# Slave_DA.net
KiCad netlist of a schematic drawn in Altium Designer
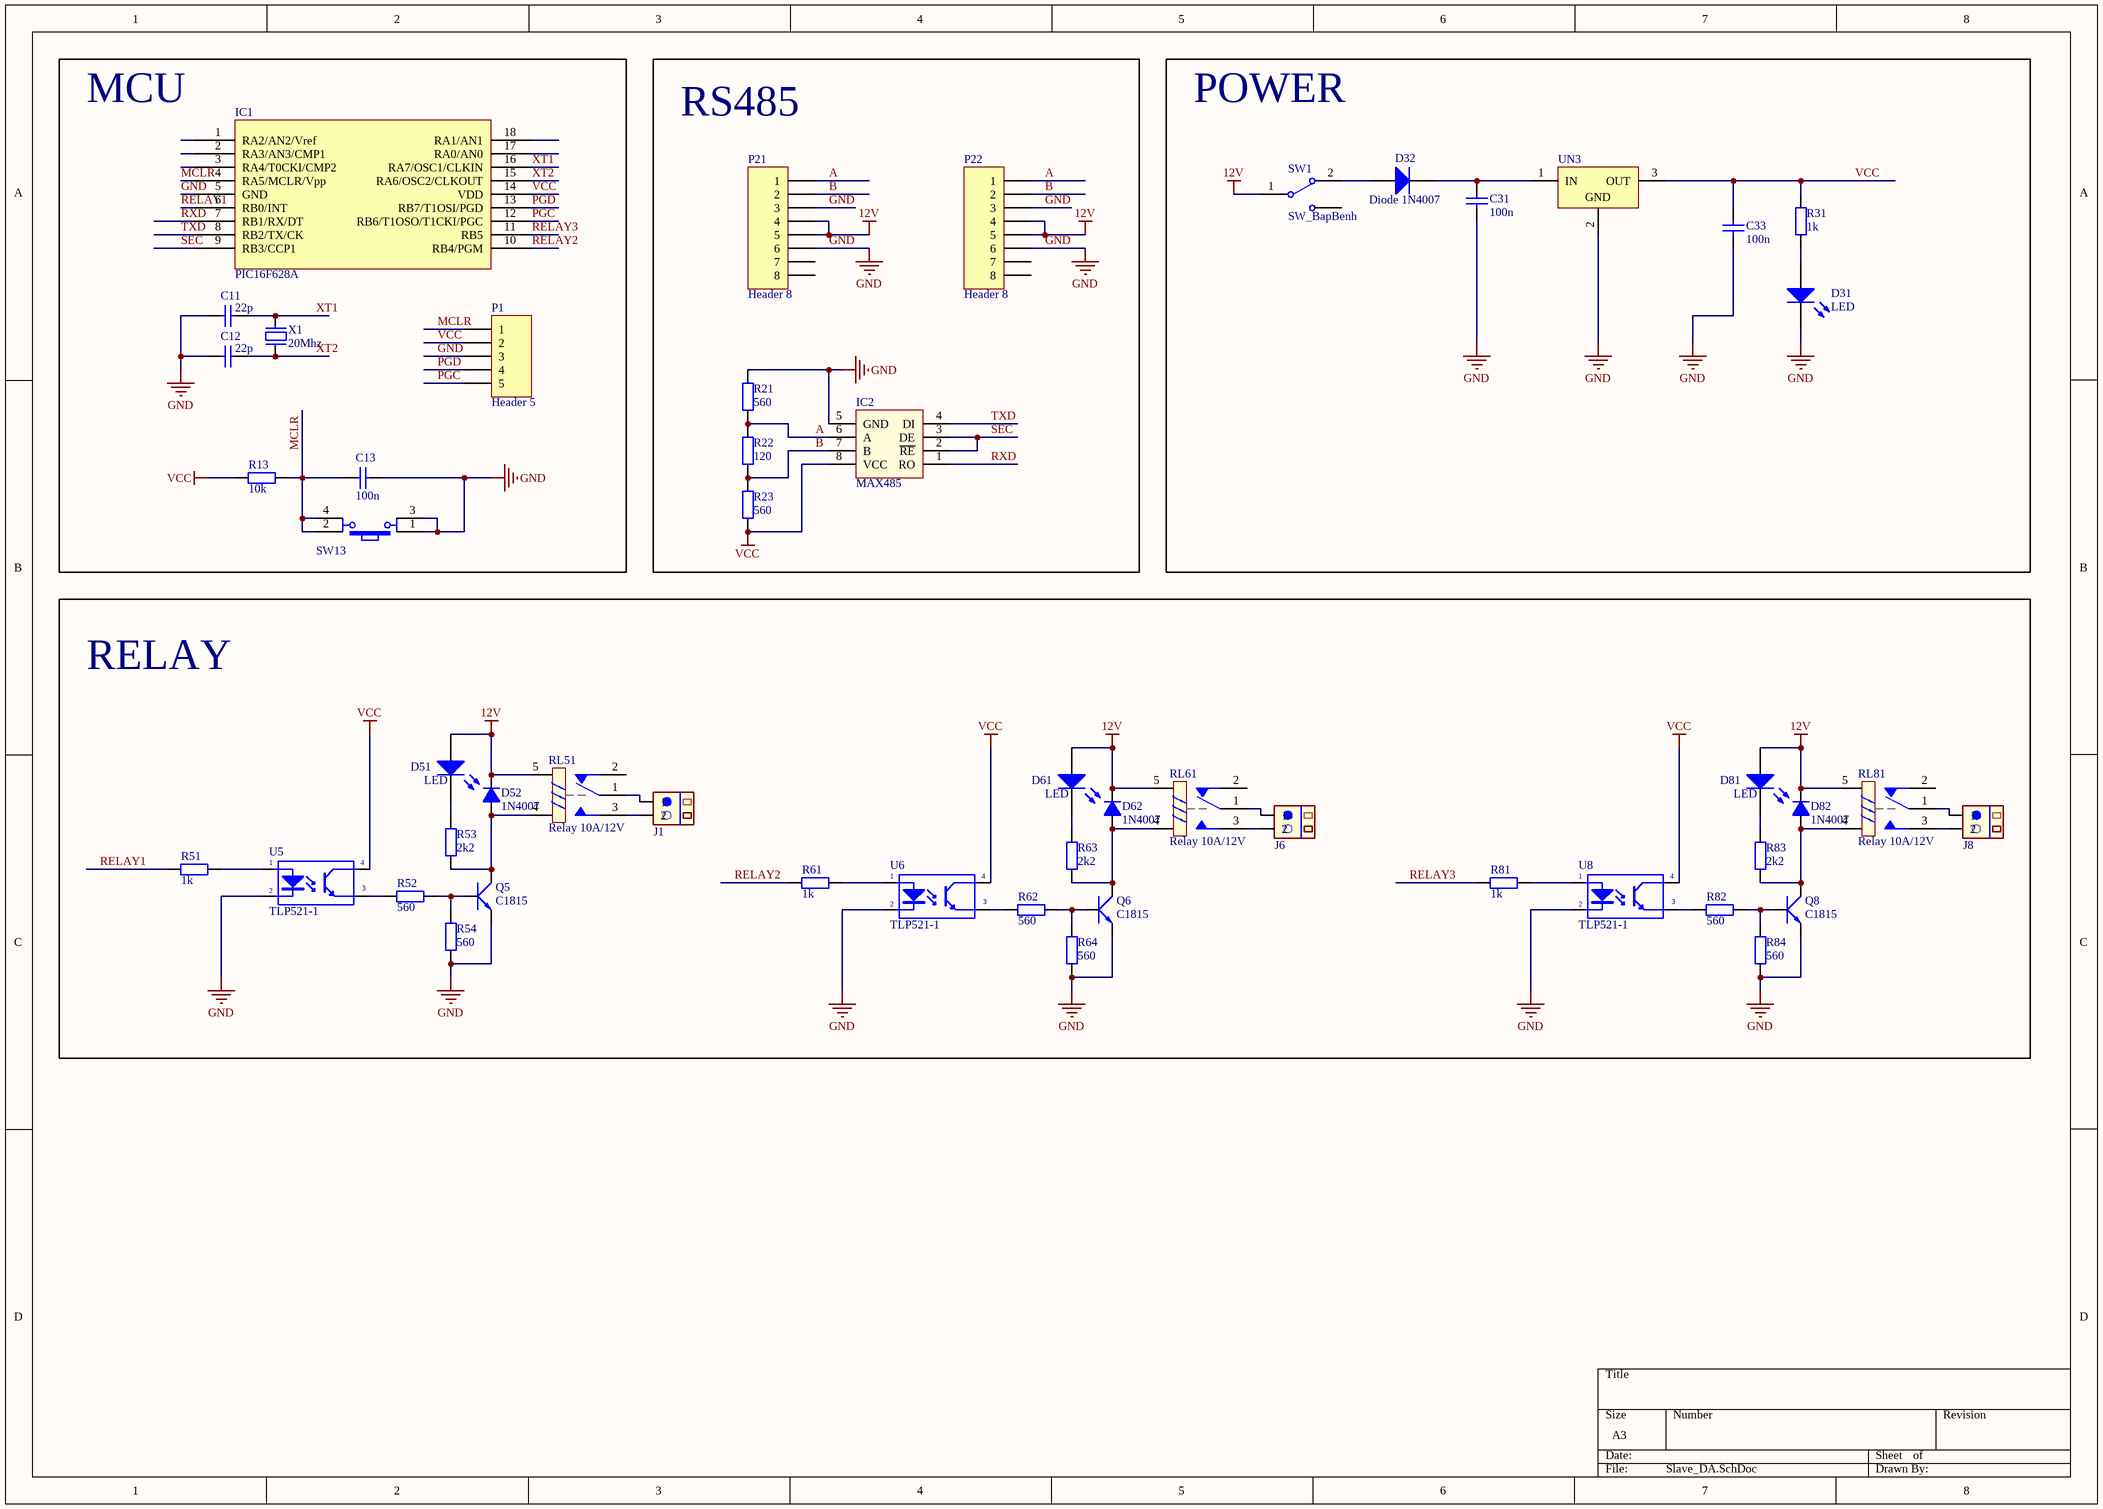
[diagram p0: Slave_DA.SchDoc]

(export (version "E")
  (design (tool "Eeschema 10.0.6"))
  (components
    (comp (ref "C11")
      (value "22p")
      (footprint "C-NP-0805")
      (description "Non-polarized Capacitor")
      (fields (field (name "Comment") "Cap Non-pol") (field (name "PUBLISHER") "Altium Limited"))
      (libsource (lib "THG") (part "Cap Non-pol"))
    )
    (comp (ref "C12")
      (value "22p")
      (footprint "C-NP-0805")
      (description "Non-polarized Capacitor")
      (fields (field (name "Comment") "Cap Non-pol") (field (name "PUBLISHER") "Altium Limited"))
      (libsource (lib "THG") (part "Cap Non-pol"))
    )
    (comp (ref "C13")
      (value "100n")
      (footprint "CAP_SMD_0805")
      (description "Capacitor")
      (fields (field (name "Comment") "Capacitor Ceramic") (field (name "PUBLISHER") "Altium Limited"))
      (libsource (lib "THG") (part "CapSMD"))
    )
    (comp (ref "C31")
      (value "100n")
      (footprint "C-NP-0805")
      (description "Non-polarized Capacitor")
      (fields (field (name "Comment") "Cap Non-pol") (field (name "PUBLISHER") "Altium Limited"))
      (libsource (lib "THG") (part "Cap Non-pol"))
    )
    (comp (ref "C33")
      (value "100n")
      (footprint "C-NP-0805")
      (description "Non-polarized Capacitor")
      (fields (field (name "Comment") "Cap Non-pol") (field (name "PUBLISHER") "Altium Limited"))
      (libsource (lib "THG") (part "Cap Non-pol"))
    )
    (comp (ref "D31")
      (value "LED")
      (footprint "LED-0805 RED")
      (description "Typical LED")
      (fields (field (name "PUBLISHER") "Altium Limited"))
      (libsource (lib "THG") (part "LED"))
    )
    (comp (ref "D32")
      (value "Diode 1N4007")
      (footprint "DO-41")
      (description "1 Amp General Purpose Rectifier")
      (fields (field (name "PUBLISHER") "Altium Limited"))
      (libsource (lib "hphonglib") (part "Diode 1N4007"))
    )
    (comp (ref "D51")
      (value "LED")
      (footprint "LED-0 5mm RED")
      (description "Typical LED")
      (fields (field (name "PUBLISHER") "Altium Limited"))
      (libsource (lib "THG") (part "LED"))
    )
    (comp (ref "D52")
      (value "1N4007")
      (footprint "D1A")
      (description "Diode 1A")
      (libsource (lib "syhaunguyen") (part "D1A"))
    )
    (comp (ref "D61")
      (value "LED")
      (footprint "LED-0 5mm RED")
      (description "Typical LED")
      (fields (field (name "PUBLISHER") "Altium Limited"))
      (libsource (lib "THG") (part "LED"))
    )
    (comp (ref "D62")
      (value "1N4007")
      (footprint "D1A")
      (description "Diode 1A")
      (libsource (lib "syhaunguyen") (part "D1A"))
    )
    (comp (ref "D81")
      (value "LED")
      (footprint "LED-0 5mm RED")
      (description "Typical LED")
      (fields (field (name "PUBLISHER") "Altium Limited"))
      (libsource (lib "THG") (part "LED"))
    )
    (comp (ref "D82")
      (value "1N4007")
      (footprint "D1A")
      (description "Diode 1A")
      (libsource (lib "syhaunguyen") (part "D1A"))
    )
    (comp (ref "IC1")
      (value "PIC16F628A")
      (footprint "DIP18/W0.3")
      (libsource (lib "THG") (part "PIC16F628A"))
    )
    (comp (ref "IC2")
      (value "MAX485")
      (footprint "DIP8/W0.3")
      (description "RS232 - RS485 (Same sn75176)")
      (libsource (lib "syhaunguyen") (part "MAX485"))
    )
    (comp (ref "J1")
      (value "CON.Domino2")
      (footprint "DOMINO 2B")
      (description "2 pins Domino Header")
      (fields (field (name "PUBLISHER") "Hoang Nguyen"))
      (libsource (lib "THG") (part "CON.Domino2"))
    )
    (comp (ref "J6")
      (value "CON.Domino2")
      (footprint "DOMINO 2B")
      (description "2 pins Domino Header")
      (fields (field (name "PUBLISHER") "Hoang Nguyen"))
      (libsource (lib "THG") (part "CON.Domino2"))
    )
    (comp (ref "J8")
      (value "CON.Domino2")
      (footprint "DOMINO 2B")
      (description "2 pins Domino Header")
      (fields (field (name "PUBLISHER") "Hoang Nguyen"))
      (libsource (lib "THG") (part "CON.Domino2"))
    )
    (comp (ref "P1")
      (value "Header 5")
      (footprint "Header 5")
      (description "Header, 5-Pin")
      (fields (field (name "PUBLISHER") "Altium Limited"))
      (libsource (lib "THG") (part "Header 5"))
    )
    (comp (ref "P21")
      (value "Header 8")
      (footprint "RJ11")
      (description "Header, 8-Pin")
      (fields (field (name "PUBLISHER") "Altium Limited"))
      (libsource (lib "THG") (part "Header 8"))
    )
    (comp (ref "P22")
      (value "Header 8")
      (footprint "RJ11")
      (description "Header, 8-Pin")
      (fields (field (name "PUBLISHER") "Altium Limited"))
      (libsource (lib "THG") (part "Header 8"))
    )
    (comp (ref "Q5")
      (value "C1815")
      (footprint "QTO-92")
      (description "NPN 600mW, ECB")
      (libsource (lib "syhaunguyen") (part "C1815"))
    )
    (comp (ref "Q6")
      (value "C1815")
      (footprint "QTO-92")
      (description "NPN 600mW, ECB")
      (libsource (lib "syhaunguyen") (part "C1815"))
    )
    (comp (ref "Q8")
      (value "C1815")
      (footprint "QTO-92")
      (description "NPN 600mW, ECB")
      (libsource (lib "syhaunguyen") (part "C1815"))
    )
    (comp (ref "R13")
      (value "10k")
      (footprint "DIEN TRO 0805")
      (description "RES_0805")
      (fields (field (name "Comment") "RES_SMD_0805") (field (name "PUBLISHER") "Altium Limited"))
      (libsource (lib "THG") (part "RES_SMD_0805"))
    )
    (comp (ref "R21")
      (value "560")
      (footprint "DIEN TRO 0805")
      (description "RES_0805")
      (fields (field (name "Comment") "RES_SMD_0805") (field (name "PUBLISHER") "Altium Limited"))
      (libsource (lib "") (part "RES_SMD_0805_2"))
    )
    (comp (ref "R22")
      (value "120")
      (footprint "DIEN TRO 0805")
      (description "RES_0805")
      (fields (field (name "Comment") "RES_SMD_0805") (field (name "PUBLISHER") "Altium Limited"))
      (libsource (lib "") (part "RES_SMD_0805_2"))
    )
    (comp (ref "R23")
      (value "560")
      (footprint "DIEN TRO 0805")
      (description "RES_0805")
      (fields (field (name "Comment") "RES_SMD_0805") (field (name "PUBLISHER") "Altium Limited"))
      (libsource (lib "") (part "RES_SMD_0805_2"))
    )
    (comp (ref "R31")
      (value "1k")
      (footprint "DIEN TRO 0805")
      (description "RES_0805")
      (fields (field (name "Comment") "RES_SMD_0805") (field (name "PUBLISHER") "Altium Limited"))
      (libsource (lib "") (part "RES_SMD_0805_2"))
    )
    (comp (ref "R51")
      (value "1k")
      (footprint "DIEN TRO 0805")
      (description "RES_0805")
      (fields (field (name "Comment") "RES_SMD_0805") (field (name "PUBLISHER") "Altium Limited"))
      (libsource (lib "THG") (part "RES_SMD_0805"))
    )
    (comp (ref "R52")
      (value "560")
      (footprint "DIEN TRO 0805")
      (description "RES_0805")
      (fields (field (name "Comment") "RES_SMD_0805") (field (name "PUBLISHER") "Altium Limited"))
      (libsource (lib "THG") (part "RES_SMD_0805"))
    )
    (comp (ref "R53")
      (value "2k2")
      (footprint "DIEN TRO 0805")
      (description "RES_0805")
      (fields (field (name "Comment") "RES_SMD_0805") (field (name "PUBLISHER") "Altium Limited"))
      (libsource (lib "") (part "RES_SMD_0805_1"))
    )
    (comp (ref "R54")
      (value "560")
      (footprint "DIEN TRO 0805")
      (description "RES_0805")
      (fields (field (name "Comment") "RES_SMD_0805") (field (name "PUBLISHER") "Altium Limited"))
      (libsource (lib "") (part "RES_SMD_0805_1"))
    )
    (comp (ref "R61")
      (value "1k")
      (footprint "DIEN TRO 0805")
      (description "RES_0805")
      (fields (field (name "Comment") "RES_SMD_0805") (field (name "PUBLISHER") "Altium Limited"))
      (libsource (lib "THG") (part "RES_SMD_0805"))
    )
    (comp (ref "R62")
      (value "560")
      (footprint "DIEN TRO 0805")
      (description "RES_0805")
      (fields (field (name "Comment") "RES_SMD_0805") (field (name "PUBLISHER") "Altium Limited"))
      (libsource (lib "THG") (part "RES_SMD_0805"))
    )
    (comp (ref "R63")
      (value "2k2")
      (footprint "DIEN TRO 0805")
      (description "RES_0805")
      (fields (field (name "Comment") "RES_SMD_0805") (field (name "PUBLISHER") "Altium Limited"))
      (libsource (lib "") (part "RES_SMD_0805_1"))
    )
    (comp (ref "R64")
      (value "560")
      (footprint "DIEN TRO 0805")
      (description "RES_0805")
      (fields (field (name "Comment") "RES_SMD_0805") (field (name "PUBLISHER") "Altium Limited"))
      (libsource (lib "") (part "RES_SMD_0805_1"))
    )
    (comp (ref "R81")
      (value "1k")
      (footprint "DIEN TRO 0805")
      (description "RES_0805")
      (fields (field (name "Comment") "RES_SMD_0805") (field (name "PUBLISHER") "Altium Limited"))
      (libsource (lib "THG") (part "RES_SMD_0805"))
    )
    (comp (ref "R82")
      (value "560")
      (footprint "DIEN TRO 0805")
      (description "RES_0805")
      (fields (field (name "Comment") "RES_SMD_0805") (field (name "PUBLISHER") "Altium Limited"))
      (libsource (lib "THG") (part "RES_SMD_0805"))
    )
    (comp (ref "R83")
      (value "2k2")
      (footprint "DIEN TRO 0805")
      (description "RES_0805")
      (fields (field (name "Comment") "RES_SMD_0805") (field (name "PUBLISHER") "Altium Limited"))
      (libsource (lib "") (part "RES_SMD_0805_1"))
    )
    (comp (ref "R84")
      (value "560")
      (footprint "DIEN TRO 0805")
      (description "RES_0805")
      (fields (field (name "Comment") "RES_SMD_0805") (field (name "PUBLISHER") "Altium Limited"))
      (libsource (lib "") (part "RES_SMD_0805_1"))
    )
    (comp (ref "RL51")
      (value "Relay 10A/12V")
      (footprint "RL_SPDT_10A")
      (description "Relay SPDT,10A - 12VDC 5 Pin")
      (libsource (lib "syhaunguyen") (part "Relay 1"))
    )
    (comp (ref "RL61")
      (value "Relay 10A/12V")
      (footprint "RL_SPDT_10A")
      (description "Relay SPDT,10A - 12VDC 5 Pin")
      (libsource (lib "syhaunguyen") (part "Relay 1"))
    )
    (comp (ref "RL81")
      (value "Relay 10A/12V")
      (footprint "RL_SPDT_10A")
      (description "Relay SPDT,10A - 12VDC 5 Pin")
      (libsource (lib "syhaunguyen") (part "Relay 1"))
    )
    (comp (ref "SW1")
      (value "SW_BapBenh")
      (footprint "SW_Bapbenh")
      (libsource (lib "THG") (part "SW_BapBenh"))
    )
    (comp (ref "SW13")
      (value "SW7")
      (footprint "SW4")
      (description "Switch button 4 pin")
      (libsource (lib "syhaunguyen") (part "SW4"))
    )
    (comp (ref "U5")
      (value "TLP521-1")
      (footprint "DIP4/W0.3")
      (description "Single Opto")
      (libsource (lib "syhaunguyen") (part "TLP521-1"))
    )
    (comp (ref "U6")
      (value "TLP521-1")
      (footprint "DIP4/W0.3")
      (description "Single Opto")
      (libsource (lib "syhaunguyen") (part "TLP521-1"))
    )
    (comp (ref "U8")
      (value "TLP521-1")
      (footprint "DIP4/W0.3")
      (description "Single Opto")
      (libsource (lib "syhaunguyen") (part "TLP521-1"))
    )
    (comp (ref "UN3")
      (value "L78M05CP")
      (footprint "QTO-220")
      (description "Positive Voltage Regulator")
      (fields (field (name "PUBLISHER") "Altium Limited"))
      (libsource (lib "syhaunguyen") (part "L78M05CP"))
    )
    (comp (ref "X1")
      (value "20Mhz")
      (footprint "XT2")
      (description "Crystal For all Crystal 2pin.")
      (libsource (lib "syhaunguyen") (part "XT2"))
    )
  )
  (nets
    (net (code "1") (name "/A") (class "Default")
      (node (ref "IC2") (pin "6") (pinfunction "A_6") (pintype "passive"))
      (node (ref "P21") (pin "1") (pinfunction "1_1") (pintype "passive"))
      (node (ref "P22") (pin "1") (pinfunction "1_1") (pintype "passive"))
      (node (ref "R21") (pin "1") (pinfunction "1_1") (pintype "passive"))
      (node (ref "R22") (pin "2") (pinfunction "2_2") (pintype "passive"))
    )
    (net (code "2") (name "/B") (class "Default")
      (node (ref "IC2") (pin "7") (pinfunction "B_7") (pintype "passive"))
      (node (ref "P21") (pin "2") (pinfunction "2_2") (pintype "passive"))
      (node (ref "P22") (pin "2") (pinfunction "2_2") (pintype "passive"))
      (node (ref "R22") (pin "1") (pinfunction "1_1") (pintype "passive"))
      (node (ref "R23") (pin "2") (pinfunction "2_2") (pintype "passive"))
    )
    (net (code "3") (name "/MCLR") (class "Default")
      (node (ref "C13") (pin "2") (pinfunction "2_2") (pintype "passive"))
      (node (ref "IC1") (pin "4") (pinfunction "RA5/MCLR/Vpp_4") (pintype "passive"))
      (node (ref "P1") (pin "1") (pinfunction "1_1") (pintype "passive"))
      (node (ref "R13") (pin "1") (pinfunction "1_1") (pintype "passive"))
      (node (ref "SW13") (pin "2") (pintype "passive"))
      (node (ref "SW13") (pin "4") (pintype "passive"))
    )
    (net (code "4") (name "/PGC") (class "Default")
      (node (ref "IC1") (pin "12") (pinfunction "RB6/T1OSO/T1CKI/PGC_12") (pintype "passive"))
      (node (ref "P1") (pin "5") (pinfunction "5_5") (pintype "passive"))
    )
    (net (code "5") (name "/PGD") (class "Default")
      (node (ref "IC1") (pin "13") (pinfunction "RB7/T1OSI/PGD_13") (pintype "passive"))
      (node (ref "P1") (pin "4") (pinfunction "4_4") (pintype "passive"))
    )
    (net (code "6") (name "/RELAY1") (class "Default")
      (node (ref "IC1") (pin "6") (pinfunction "RB0/INT_6") (pintype "passive"))
      (node (ref "R51") (pin "2") (pinfunction "2_2") (pintype "passive"))
    )
    (net (code "7") (name "/RELAY2") (class "Default")
      (node (ref "IC1") (pin "10") (pinfunction "RB4/PGM_10") (pintype "passive"))
      (node (ref "R61") (pin "2") (pinfunction "2_2") (pintype "passive"))
    )
    (net (code "8") (name "/RELAY3") (class "Default")
      (node (ref "IC1") (pin "11") (pinfunction "RB5_11") (pintype "passive"))
      (node (ref "R81") (pin "2") (pinfunction "2_2") (pintype "passive"))
    )
    (net (code "9") (name "/RXD") (class "Default")
      (node (ref "IC1") (pin "7") (pinfunction "RB1/RX/DT_7") (pintype "passive"))
      (node (ref "IC2") (pin "1") (pinfunction "RO_1") (pintype "passive"))
    )
    (net (code "10") (name "/SEC") (class "Default")
      (node (ref "IC1") (pin "9") (pinfunction "RB3/CCP1_9") (pintype "passive"))
      (node (ref "IC2") (pin "2") (pinfunction "~{RE}_2") (pintype "passive"))
      (node (ref "IC2") (pin "3") (pinfunction "DE_3") (pintype "passive"))
    )
    (net (code "11") (name "/TXD") (class "Default")
      (node (ref "IC1") (pin "8") (pinfunction "RB2/TX/CK_8") (pintype "passive"))
      (node (ref "IC2") (pin "4") (pinfunction "DI_4") (pintype "passive"))
    )
    (net (code "12") (name "/XT1") (class "Default")
      (node (ref "C11") (pin "1") (pinfunction "1_1") (pintype "passive"))
      (node (ref "IC1") (pin "16") (pinfunction "RA7/OSC1/CLKIN_16") (pintype "passive"))
      (node (ref "X1") (pin "2") (pinfunction "2_2") (pintype "passive"))
    )
    (net (code "13") (name "/XT2") (class "Default")
      (node (ref "C12") (pin "1") (pinfunction "1_1") (pintype "passive"))
      (node (ref "IC1") (pin "15") (pinfunction "RA6/OSC2/CLKOUT_15") (pintype "passive"))
      (node (ref "X1") (pin "1") (pinfunction "1_1") (pintype "passive"))
    )
    (net (code "14") (name "12V") (class "Default")
      (node (ref "D51") (pin "1") (pinfunction "A_1") (pintype "passive"))
      (node (ref "D52") (pin "2") (pinfunction "K_2") (pintype "passive"))
      (node (ref "D61") (pin "1") (pinfunction "A_1") (pintype "passive"))
      (node (ref "D62") (pin "2") (pinfunction "K_2") (pintype "passive"))
      (node (ref "D81") (pin "1") (pinfunction "A_1") (pintype "passive"))
      (node (ref "D82") (pin "2") (pinfunction "K_2") (pintype "passive"))
      (node (ref "P21") (pin "4") (pinfunction "4_4") (pintype "passive"))
      (node (ref "P21") (pin "5") (pinfunction "5_5") (pintype "passive"))
      (node (ref "P22") (pin "4") (pinfunction "4_4") (pintype "passive"))
      (node (ref "P22") (pin "5") (pinfunction "5_5") (pintype "passive"))
      (node (ref "RL51") (pin "5") (pinfunction "5_5") (pintype "passive"))
      (node (ref "RL61") (pin "5") (pinfunction "5_5") (pintype "passive"))
      (node (ref "RL81") (pin "5") (pinfunction "5_5") (pintype "passive"))
      (node (ref "SW1") (pin "1") (pinfunction "1_1") (pintype "passive"))
    )
    (net (code "15") (name "GND") (class "Default")
      (node (ref "C11") (pin "2") (pinfunction "2_2") (pintype "passive"))
      (node (ref "C12") (pin "2") (pinfunction "2_2") (pintype "passive"))
      (node (ref "C13") (pin "1") (pinfunction "1_1") (pintype "passive"))
      (node (ref "C31") (pin "1") (pinfunction "1_1") (pintype "passive"))
      (node (ref "C33") (pin "1") (pinfunction "1_1") (pintype "passive"))
      (node (ref "D31") (pin "2") (pinfunction "K_2") (pintype "passive"))
      (node (ref "IC1") (pin "5") (pinfunction "GND_5") (pintype "passive"))
      (node (ref "IC2") (pin "5") (pinfunction "GND_5") (pintype "passive"))
      (node (ref "P1") (pin "3") (pinfunction "3_3") (pintype "passive"))
      (node (ref "P21") (pin "3") (pinfunction "3_3") (pintype "passive"))
      (node (ref "P21") (pin "6") (pinfunction "6_6") (pintype "passive"))
      (node (ref "P22") (pin "3") (pinfunction "3_3") (pintype "passive"))
      (node (ref "P22") (pin "6") (pinfunction "6_6") (pintype "passive"))
      (node (ref "Q5") (pin "1") (pinfunction "E_1") (pintype "passive"))
      (node (ref "Q6") (pin "1") (pinfunction "E_1") (pintype "passive"))
      (node (ref "Q8") (pin "1") (pinfunction "E_1") (pintype "passive"))
      (node (ref "R21") (pin "2") (pinfunction "2_2") (pintype "passive"))
      (node (ref "R54") (pin "2") (pinfunction "2_2") (pintype "passive"))
      (node (ref "R64") (pin "2") (pinfunction "2_2") (pintype "passive"))
      (node (ref "R84") (pin "2") (pinfunction "2_2") (pintype "passive"))
      (node (ref "SW13") (pin "1") (pintype "passive"))
      (node (ref "SW13") (pin "3") (pintype "passive"))
      (node (ref "U5") (pin "2") (pinfunction "K_2") (pintype "passive"))
      (node (ref "U6") (pin "2") (pinfunction "K_2") (pintype "passive"))
      (node (ref "U8") (pin "2") (pinfunction "K_2") (pintype "passive"))
      (node (ref "UN3") (pin "2") (pinfunction "GND_2") (pintype "power_in"))
    )
    (net (code "16") (name "Net-(D31-A)") (class "Default")
      (node (ref "D31") (pin "1") (pinfunction "A_1") (pintype "passive"))
      (node (ref "R31") (pin "1") (pinfunction "1_1") (pintype "passive"))
    )
    (net (code "17") (name "Net-(D32-A)") (class "Default")
      (node (ref "D32") (pin "1") (pinfunction "A_1") (pintype "passive"))
      (node (ref "SW1") (pin "2") (pinfunction "2_2") (pintype "passive"))
    )
    (net (code "18") (name "Net-(D32-K)") (class "Default")
      (node (ref "C31") (pin "2") (pinfunction "2_2") (pintype "passive"))
      (node (ref "D32") (pin "2") (pinfunction "K_2") (pintype "passive"))
      (node (ref "UN3") (pin "1") (pinfunction "IN_1") (pintype "power_in"))
    )
    (net (code "19") (name "Net-(D51-K)") (class "Default")
      (node (ref "D51") (pin "2") (pinfunction "K_2") (pintype "passive"))
      (node (ref "R53") (pin "1") (pinfunction "1_1") (pintype "passive"))
    )
    (net (code "20") (name "Net-(D52-A)") (class "Default")
      (node (ref "D52") (pin "1") (pinfunction "A_1") (pintype "passive"))
      (node (ref "Q5") (pin "2") (pinfunction "C_2") (pintype "passive"))
      (node (ref "R53") (pin "2") (pinfunction "2_2") (pintype "passive"))
      (node (ref "RL51") (pin "4") (pinfunction "4_4") (pintype "passive"))
    )
    (net (code "21") (name "Net-(D61-K)") (class "Default")
      (node (ref "D61") (pin "2") (pinfunction "K_2") (pintype "passive"))
      (node (ref "R63") (pin "1") (pinfunction "1_1") (pintype "passive"))
    )
    (net (code "22") (name "Net-(D62-A)") (class "Default")
      (node (ref "D62") (pin "1") (pinfunction "A_1") (pintype "passive"))
      (node (ref "Q6") (pin "2") (pinfunction "C_2") (pintype "passive"))
      (node (ref "R63") (pin "2") (pinfunction "2_2") (pintype "passive"))
      (node (ref "RL61") (pin "4") (pinfunction "4_4") (pintype "passive"))
    )
    (net (code "23") (name "Net-(D81-K)") (class "Default")
      (node (ref "D81") (pin "2") (pinfunction "K_2") (pintype "passive"))
      (node (ref "R83") (pin "1") (pinfunction "1_1") (pintype "passive"))
    )
    (net (code "24") (name "Net-(D82-A)") (class "Default")
      (node (ref "D82") (pin "1") (pinfunction "A_1") (pintype "passive"))
      (node (ref "Q8") (pin "2") (pinfunction "C_2") (pintype "passive"))
      (node (ref "R83") (pin "2") (pinfunction "2_2") (pintype "passive"))
      (node (ref "RL81") (pin "4") (pinfunction "4_4") (pintype "passive"))
    )
    (net (code "25") (name "Net-(J1-Pad1)") (class "Default")
      (node (ref "J1") (pin "1") (pinfunction "1_1") (pintype "passive"))
      (node (ref "RL51") (pin "1") (pinfunction "1_1") (pintype "passive"))
    )
    (net (code "26") (name "Net-(J1-Pad2)") (class "Default")
      (node (ref "J1") (pin "2") (pinfunction "2_2") (pintype "passive"))
      (node (ref "RL51") (pin "3") (pinfunction "3_3") (pintype "passive"))
    )
    (net (code "27") (name "Net-(J6-Pad1)") (class "Default")
      (node (ref "J6") (pin "1") (pinfunction "1_1") (pintype "passive"))
      (node (ref "RL61") (pin "1") (pinfunction "1_1") (pintype "passive"))
    )
    (net (code "28") (name "Net-(J6-Pad2)") (class "Default")
      (node (ref "J6") (pin "2") (pinfunction "2_2") (pintype "passive"))
      (node (ref "RL61") (pin "3") (pinfunction "3_3") (pintype "passive"))
    )
    (net (code "29") (name "Net-(J8-Pad1)") (class "Default")
      (node (ref "J8") (pin "1") (pinfunction "1_1") (pintype "passive"))
      (node (ref "RL81") (pin "1") (pinfunction "1_1") (pintype "passive"))
    )
    (net (code "30") (name "Net-(J8-Pad2)") (class "Default")
      (node (ref "J8") (pin "2") (pinfunction "2_2") (pintype "passive"))
      (node (ref "RL81") (pin "3") (pinfunction "3_3") (pintype "passive"))
    )
    (net (code "31") (name "Net-(Q5-B)") (class "Default")
      (node (ref "Q5") (pin "3") (pinfunction "B_3") (pintype "passive"))
      (node (ref "R52") (pin "1") (pinfunction "1_1") (pintype "passive"))
      (node (ref "R54") (pin "1") (pinfunction "1_1") (pintype "passive"))
    )
    (net (code "32") (name "Net-(Q6-B)") (class "Default")
      (node (ref "Q6") (pin "3") (pinfunction "B_3") (pintype "passive"))
      (node (ref "R62") (pin "1") (pinfunction "1_1") (pintype "passive"))
      (node (ref "R64") (pin "1") (pinfunction "1_1") (pintype "passive"))
    )
    (net (code "33") (name "Net-(Q8-B)") (class "Default")
      (node (ref "Q8") (pin "3") (pinfunction "B_3") (pintype "passive"))
      (node (ref "R82") (pin "1") (pinfunction "1_1") (pintype "passive"))
      (node (ref "R84") (pin "1") (pinfunction "1_1") (pintype "passive"))
    )
    (net (code "34") (name "Net-(U5-A)") (class "Default")
      (node (ref "R51") (pin "1") (pinfunction "1_1") (pintype "passive"))
      (node (ref "U5") (pin "1") (pinfunction "A_1") (pintype "passive"))
    )
    (net (code "35") (name "Net-(U5-E)") (class "Default")
      (node (ref "R52") (pin "2") (pinfunction "2_2") (pintype "passive"))
      (node (ref "U5") (pin "3") (pinfunction "E_3") (pintype "passive"))
    )
    (net (code "36") (name "Net-(U6-A)") (class "Default")
      (node (ref "R61") (pin "1") (pinfunction "1_1") (pintype "passive"))
      (node (ref "U6") (pin "1") (pinfunction "A_1") (pintype "passive"))
    )
    (net (code "37") (name "Net-(U6-E)") (class "Default")
      (node (ref "R62") (pin "2") (pinfunction "2_2") (pintype "passive"))
      (node (ref "U6") (pin "3") (pinfunction "E_3") (pintype "passive"))
    )
    (net (code "38") (name "Net-(U8-A)") (class "Default")
      (node (ref "R81") (pin "1") (pinfunction "1_1") (pintype "passive"))
      (node (ref "U8") (pin "1") (pinfunction "A_1") (pintype "passive"))
    )
    (net (code "39") (name "Net-(U8-E)") (class "Default")
      (node (ref "R82") (pin "2") (pinfunction "2_2") (pintype "passive"))
      (node (ref "U8") (pin "3") (pinfunction "E_3") (pintype "passive"))
    )
    (net (code "40") (name "VCC") (class "Default")
      (node (ref "C33") (pin "2") (pinfunction "2_2") (pintype "passive"))
      (node (ref "IC1") (pin "14") (pinfunction "VDD_14") (pintype "passive"))
      (node (ref "IC2") (pin "8") (pinfunction "VCC_8") (pintype "passive"))
      (node (ref "P1") (pin "2") (pinfunction "2_2") (pintype "passive"))
      (node (ref "R13") (pin "2") (pinfunction "2_2") (pintype "passive"))
      (node (ref "R23") (pin "1") (pinfunction "1_1") (pintype "passive"))
      (node (ref "R31") (pin "2") (pinfunction "2_2") (pintype "passive"))
      (node (ref "U5") (pin "4") (pinfunction "C_4") (pintype "passive"))
      (node (ref "U6") (pin "4") (pinfunction "C_4") (pintype "passive"))
      (node (ref "U8") (pin "4") (pinfunction "C_4") (pintype "passive"))
      (node (ref "UN3") (pin "3") (pinfunction "OUT_3") (pintype "power_in"))
    )
    (net (code "41") (name "unconnected-(IC1-RA0{slash}AN0-Pad17)") (class "Default")
      (node (ref "IC1") (pin "17") (pinfunction "RA0/AN0_17") (pintype "passive"))
    )
    (net (code "42") (name "unconnected-(IC1-RA1{slash}AN1-Pad18)") (class "Default")
      (node (ref "IC1") (pin "18") (pinfunction "RA1/AN1_18") (pintype "passive"))
    )
    (net (code "43") (name "unconnected-(IC1-RA2{slash}AN2{slash}Vref-Pad1)") (class "Default")
      (node (ref "IC1") (pin "1") (pinfunction "RA2/AN2/Vref_1") (pintype "passive"))
    )
    (net (code "44") (name "unconnected-(IC1-RA3{slash}AN3{slash}CMP1-Pad2)") (class "Default")
      (node (ref "IC1") (pin "2") (pinfunction "RA3/AN3/CMP1_2") (pintype "passive"))
    )
    (net (code "45") (name "unconnected-(IC1-RA4{slash}T0CKI{slash}CMP2-Pad3)") (class "Default")
      (node (ref "IC1") (pin "3") (pinfunction "RA4/T0CKI/CMP2_3") (pintype "passive"))
    )
    (net (code "46") (name "unconnected-(P21-Pad7)") (class "Default")
      (node (ref "P21") (pin "7") (pinfunction "7_7") (pintype "passive"))
    )
    (net (code "47") (name "unconnected-(P21-Pad8)") (class "Default")
      (node (ref "P21") (pin "8") (pinfunction "8_8") (pintype "passive"))
    )
    (net (code "48") (name "unconnected-(P22-Pad7)") (class "Default")
      (node (ref "P22") (pin "7") (pinfunction "7_7") (pintype "passive"))
    )
    (net (code "49") (name "unconnected-(P22-Pad8)") (class "Default")
      (node (ref "P22") (pin "8") (pinfunction "8_8") (pintype "passive"))
    )
    (net (code "50") (name "unconnected-(RL51-Pad2)") (class "Default")
      (node (ref "RL51") (pin "2") (pinfunction "2_2") (pintype "passive"))
    )
    (net (code "51") (name "unconnected-(RL61-Pad2)") (class "Default")
      (node (ref "RL61") (pin "2") (pinfunction "2_2") (pintype "passive"))
    )
    (net (code "52") (name "unconnected-(RL81-Pad2)") (class "Default")
      (node (ref "RL81") (pin "2") (pinfunction "2_2") (pintype "passive"))
    )
  )
)
